# USBasp.net
KiCad netlist of a schematic drawn in EAGLE
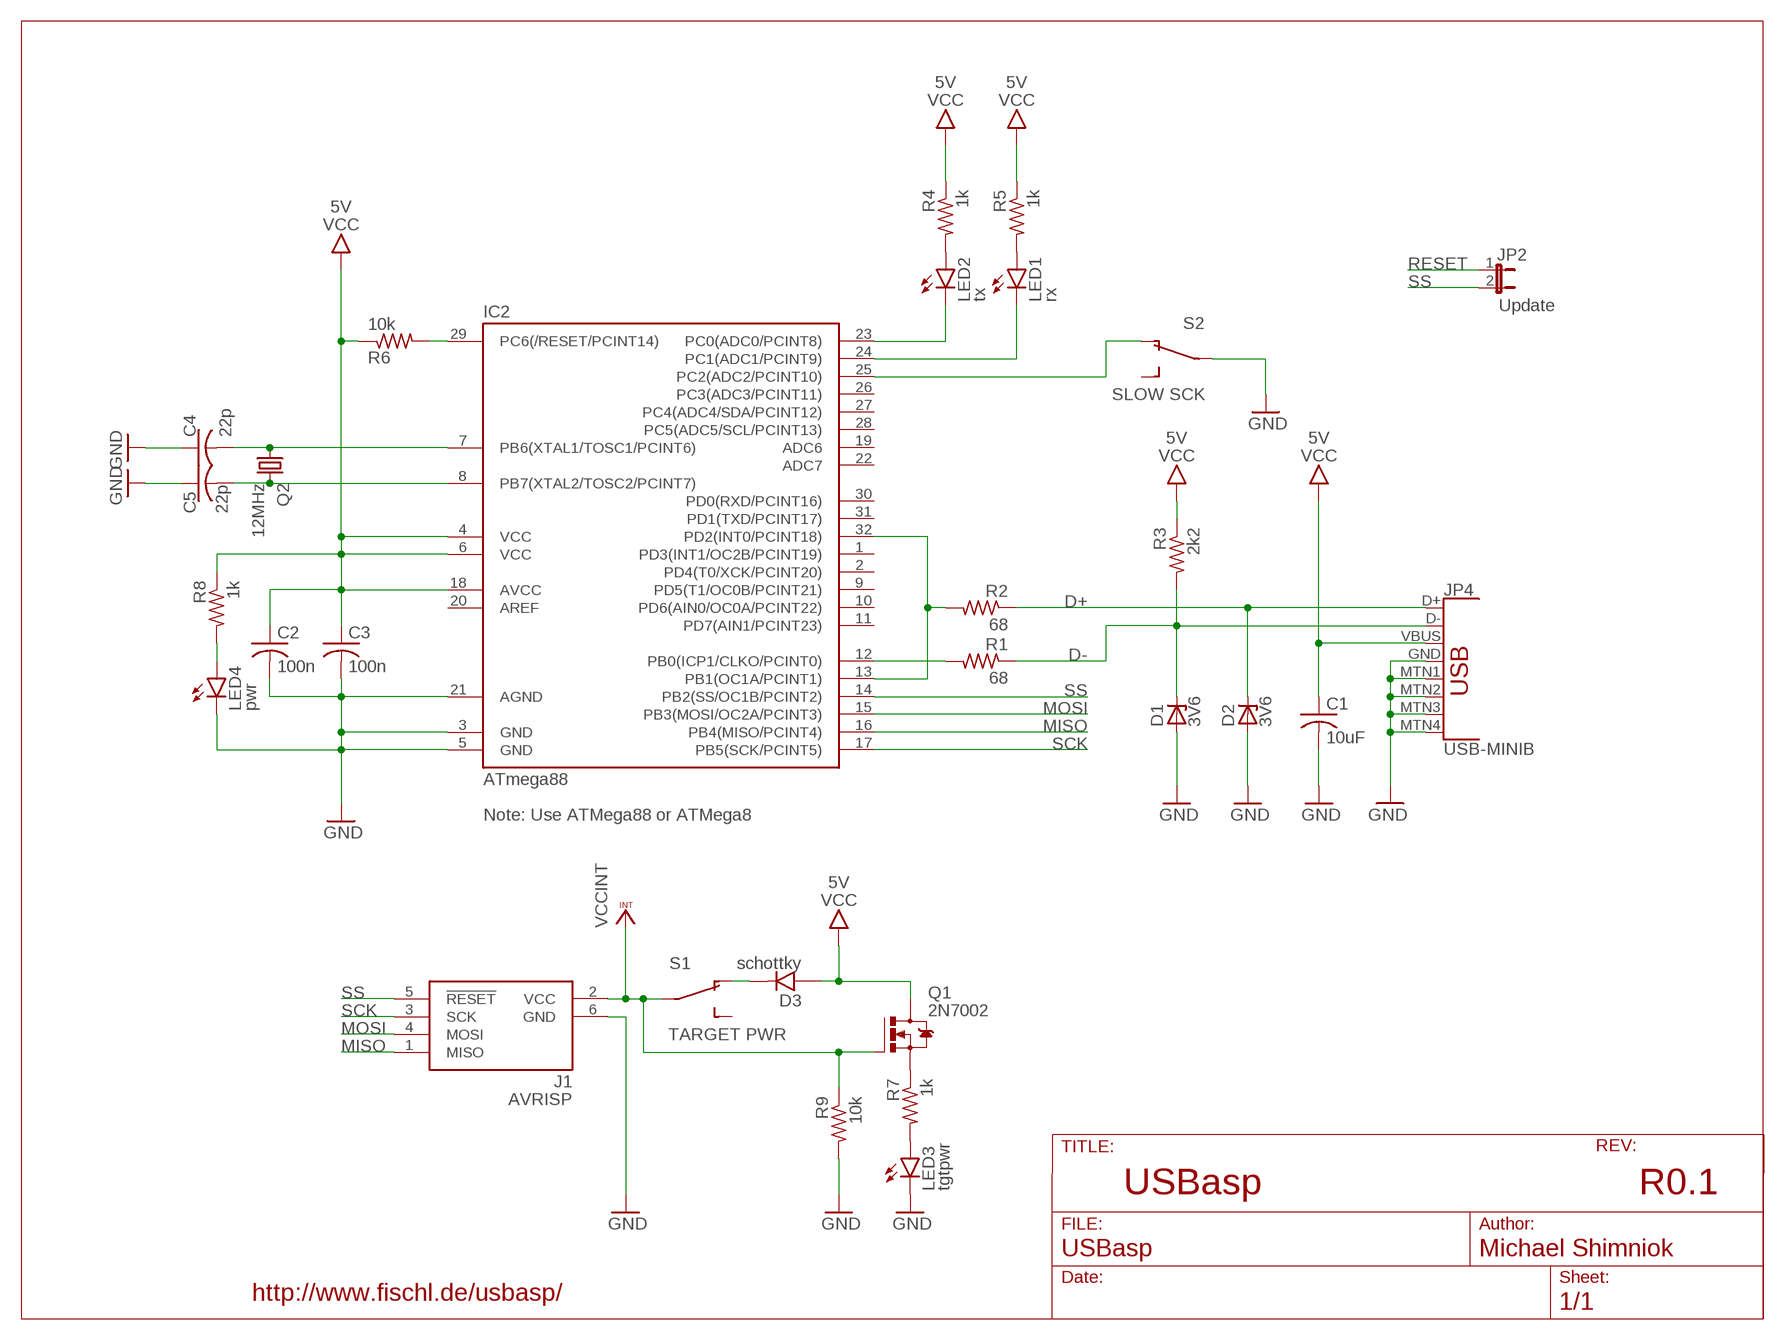
[diagram p0: schematic, sheet 1]

(export (version "E")
  (design (tool "Eeschema 10.0.6"))
  (components
    (comp (ref "C1")
      (value "10uF")
      (footprint "eagle-import:1206")
      (libsource (lib "eagle-import") (part "C-1206"))
    )
    (comp (ref "C2")
      (value "100n")
      (footprint "eagle-import:0603")
      (libsource (lib "eagle-import") (part "C-0603"))
    )
    (comp (ref "C3")
      (value "100n")
      (footprint "eagle-import:0603")
      (libsource (lib "eagle-import") (part "C-0603"))
    )
    (comp (ref "C4")
      (value "22p")
      (footprint "eagle-import:0603")
      (libsource (lib "eagle-import") (part "C-0603"))
    )
    (comp (ref "C5")
      (value "22p")
      (footprint "eagle-import:0603")
      (libsource (lib "eagle-import") (part "C-0603"))
    )
    (comp (ref "D1")
      (value "3V6")
      (footprint "eagle-import:SOD80C")
      (libsource (lib "eagle-import") (part "ZENER-DIODESOD80C"))
    )
    (comp (ref "D2")
      (value "3V6")
      (footprint "eagle-import:SOD80C")
      (libsource (lib "eagle-import") (part "ZENER-DIODESOD80C"))
    )
    (comp (ref "D3")
      (value "schottky")
      (footprint "eagle-import:SOD123FL")
      (libsource (lib "eagle-import") (part "DIODE_SOD123FL"))
    )
    (comp (ref "IC2")
      (value "ATmega88")
      (footprint "eagle-import:TQFP32-08")
      (libsource (lib "eagle-import") (part "MEGA48/88/168-AU"))
    )
    (comp (ref "J1")
      (value "AVRISP")
      (footprint "eagle-import:CON6P2R")
      (libsource (lib "eagle-import") (part "AVRISP6_COMPACT"))
    )
    (comp (ref "JP2")
      (value "Update")
      (footprint "eagle-import:JP1")
      (libsource (lib "eagle-import") (part "JP1E"))
    )
    (comp (ref "JP4")
      (value "USB-MINIB")
      (footprint "eagle-import:USB-MINIB")
      (libsource (lib "eagle-import") (part "USB-MINIB"))
    )
    (comp (ref "LED1")
      (value "rx")
      (footprint "eagle-import:CHIPLED_1206")
      (libsource (lib "eagle-import") (part "LEDCHIPLED_1206"))
    )
    (comp (ref "LED2")
      (value "tx")
      (footprint "eagle-import:CHIPLED_1206")
      (libsource (lib "eagle-import") (part "LEDCHIPLED_1206"))
    )
    (comp (ref "LED3")
      (value "tgtpwr")
      (footprint "eagle-import:CHIPLED_1206")
      (libsource (lib "eagle-import") (part "LEDCHIPLED_1206"))
    )
    (comp (ref "LED4")
      (value "pwr")
      (footprint "eagle-import:CHIPLED_1206")
      (libsource (lib "eagle-import") (part "LEDCHIPLED_1206"))
    )
    (comp (ref "Q1")
      (value "2N7002")
      (footprint "eagle-import:SOT-23")
      (libsource (lib "eagle-import") (part "MOSFET-N-SOT23"))
    )
    (comp (ref "Q2")
      (value "12MHz")
      (footprint "eagle-import:NDK_2PAD_5X3")
      (libsource (lib "eagle-import") (part "CRYSTALNDK5X3"))
    )
    (comp (ref "R1")
      (value "68")
      (footprint "eagle-import:0603")
      (libsource (lib "eagle-import") (part "R0603"))
    )
    (comp (ref "R2")
      (value "68")
      (footprint "eagle-import:0603")
      (libsource (lib "eagle-import") (part "R0603"))
    )
    (comp (ref "R3")
      (value "2k2")
      (footprint "eagle-import:0603")
      (libsource (lib "eagle-import") (part "R0603"))
    )
    (comp (ref "R4")
      (value "1k")
      (footprint "eagle-import:0603")
      (libsource (lib "eagle-import") (part "R0603"))
    )
    (comp (ref "R5")
      (value "1k")
      (footprint "eagle-import:0603")
      (libsource (lib "eagle-import") (part "R0603"))
    )
    (comp (ref "R6")
      (value "10k")
      (footprint "eagle-import:0603")
      (libsource (lib "eagle-import") (part "R0603"))
    )
    (comp (ref "R7")
      (value "1k")
      (footprint "eagle-import:0603")
      (libsource (lib "eagle-import") (part "R0603"))
    )
    (comp (ref "R8")
      (value "1k")
      (footprint "eagle-import:0603")
      (libsource (lib "eagle-import") (part "R0603"))
    )
    (comp (ref "R9")
      (value "10k")
      (footprint "eagle-import:0603")
      (libsource (lib "eagle-import") (part "R0603"))
    )
    (comp (ref "S1")
      (value "TARGET PWR")
      (footprint "eagle-import:OS102011MA1Q")
      (libsource (lib "eagle-import") (part "SPDT_OS102011MAQN1"))
    )
    (comp (ref "S2")
      (value "SLOW SCK")
      (footprint "eagle-import:OS102011MA1Q")
      (libsource (lib "eagle-import") (part "SPDT_OS102011MAQN1"))
    )
  )
  (nets
    (net (code "1") (name "/D+") (class "Default")
      (node (ref "D2") (pin "C") (pinfunction "C_C") (pintype "passive"))
      (node (ref "JP4") (pin "D+") (pinfunction "D+_D+") (pintype "bidirectional"))
      (node (ref "R2") (pin "1") (pinfunction "1_1") (pintype "passive"))
    )
    (net (code "2") (name "/D-") (class "Default")
      (node (ref "D1") (pin "C") (pinfunction "C_C") (pintype "passive"))
      (node (ref "JP4") (pin "D-") (pinfunction "D-_D-") (pintype "bidirectional"))
      (node (ref "R1") (pin "1") (pinfunction "1_1") (pintype "passive"))
      (node (ref "R3") (pin "2") (pinfunction "2_2") (pintype "passive"))
    )
    (net (code "3") (name "/MISO") (class "Default")
      (node (ref "IC2") (pin "16") (pinfunction "PB4(MISO/PCINT4)_16") (pintype "bidirectional"))
      (node (ref "J1") (pin "1") (pinfunction "MISO_1") (pintype "input"))
    )
    (net (code "4") (name "/MOSI") (class "Default")
      (node (ref "IC2") (pin "15") (pinfunction "PB3(MOSI/OC2A/PCINT3)_15") (pintype "bidirectional"))
      (node (ref "J1") (pin "4") (pinfunction "MOSI_4") (pintype "output"))
    )
    (net (code "5") (name "/RESET") (class "Default")
      (node (ref "IC2") (pin "29") (pinfunction "PC6(/RESET/PCINT14)_29") (pintype "bidirectional"))
      (node (ref "JP2") (pin "1") (pinfunction "1_1") (pintype "passive"))
      (node (ref "R6") (pin "2") (pinfunction "2_2") (pintype "passive"))
    )
    (net (code "6") (name "/SCK") (class "Default")
      (node (ref "IC2") (pin "17") (pinfunction "PB5(SCK/PCINT5)_17") (pintype "bidirectional"))
      (node (ref "J1") (pin "3") (pinfunction "SCK_3") (pintype "output"))
    )
    (net (code "7") (name "/SS") (class "Default")
      (node (ref "IC2") (pin "14") (pinfunction "PB2(SS/OC1B/PCINT2)_14") (pintype "bidirectional"))
      (node (ref "J1") (pin "5") (pinfunction "~{RESET}_5") (pintype "output"))
      (node (ref "JP2") (pin "2") (pinfunction "2_2") (pintype "passive"))
    )
    (net (code "8") (name "5V") (class "Default")
      (node (ref "C1") (pin "1") (pinfunction "+_1") (pintype "passive"))
      (node (ref "C2") (pin "1") (pinfunction "+_1") (pintype "passive"))
      (node (ref "C3") (pin "1") (pinfunction "+_1") (pintype "passive"))
      (node (ref "D3") (pin "A") (pinfunction "A_A") (pintype "passive"))
      (node (ref "IC2") (pin "18") (pinfunction "AVCC_18") (pintype "passive"))
      (node (ref "IC2") (pin "4") (pinfunction "VCC_4") (pintype "power_in"))
      (node (ref "IC2") (pin "6") (pinfunction "VCC_6") (pintype "power_in"))
      (node (ref "JP4") (pin "VBUS") (pinfunction "VBUS_VBUS") (pintype "bidirectional"))
      (node (ref "Q1") (pin "3") (pinfunction "D_3") (pintype "passive"))
      (node (ref "R3") (pin "1") (pinfunction "1_1") (pintype "passive"))
      (node (ref "R4") (pin "1") (pinfunction "1_1") (pintype "passive"))
      (node (ref "R5") (pin "1") (pinfunction "1_1") (pintype "passive"))
      (node (ref "R6") (pin "1") (pinfunction "1_1") (pintype "passive"))
      (node (ref "R8") (pin "1") (pinfunction "1_1") (pintype "passive"))
    )
    (net (code "9") (name "GND") (class "Default")
      (node (ref "C1") (pin "2") (pinfunction "-_2") (pintype "passive"))
      (node (ref "C2") (pin "2") (pinfunction "-_2") (pintype "passive"))
      (node (ref "C3") (pin "2") (pinfunction "-_2") (pintype "passive"))
      (node (ref "C4") (pin "1") (pinfunction "+_1") (pintype "passive"))
      (node (ref "C5") (pin "1") (pinfunction "+_1") (pintype "passive"))
      (node (ref "D1") (pin "A") (pinfunction "A_A") (pintype "passive"))
      (node (ref "D2") (pin "A") (pinfunction "A_A") (pintype "passive"))
      (node (ref "IC2") (pin "21") (pinfunction "AGND_21") (pintype "power_in"))
      (node (ref "IC2") (pin "3") (pinfunction "GND_3") (pintype "power_in"))
      (node (ref "IC2") (pin "5") (pinfunction "GND_5") (pintype "power_in"))
      (node (ref "J1") (pin "6") (pinfunction "GND_6") (pintype "power_in"))
      (node (ref "JP4") (pin "GND") (pinfunction "GND_GND") (pintype "bidirectional"))
      (node (ref "JP4") (pin "MTN1") (pinfunction "SHIELD1_MTN1") (pintype "bidirectional"))
      (node (ref "JP4") (pin "MTN2") (pinfunction "SHIELD2_MTN2") (pintype "bidirectional"))
      (node (ref "JP4") (pin "MTN3") (pinfunction "SHIELD3_MTN3") (pintype "bidirectional"))
      (node (ref "JP4") (pin "MTN4") (pinfunction "SHIELD4_MTN4") (pintype "bidirectional"))
      (node (ref "LED3") (pin "C") (pinfunction "C_C") (pintype "passive"))
      (node (ref "LED4") (pin "C") (pinfunction "C_C") (pintype "passive"))
      (node (ref "R9") (pin "2") (pinfunction "2_2") (pintype "passive"))
      (node (ref "S2") (pin "2") (pinfunction "P_2") (pintype "passive"))
    )
    (net (code "10") (name "Net-(C4--)") (class "Default")
      (node (ref "C4") (pin "2") (pinfunction "-_2") (pintype "passive"))
      (node (ref "IC2") (pin "7") (pinfunction "PB6(XTAL1/TOSC1/PCINT6)_7") (pintype "bidirectional"))
      (node (ref "Q2") (pin "P$1") (pinfunction "1_P$1") (pintype "passive"))
    )
    (net (code "11") (name "Net-(C5--)") (class "Default")
      (node (ref "C5") (pin "2") (pinfunction "-_2") (pintype "passive"))
      (node (ref "IC2") (pin "8") (pinfunction "PB7(XTAL2/TOSC2/PCINT7)_8") (pintype "bidirectional"))
      (node (ref "Q2") (pin "P$2") (pinfunction "2_P$2") (pintype "passive"))
    )
    (net (code "12") (name "Net-(IC2-PB0(ICP1{slash}CLKO{slash}PCINT0))") (class "Default")
      (node (ref "IC2") (pin "12") (pinfunction "PB0(ICP1/CLKO/PCINT0)_12") (pintype "bidirectional"))
      (node (ref "R1") (pin "2") (pinfunction "2_2") (pintype "passive"))
    )
    (net (code "13") (name "Net-(IC2-PB1(OC1A{slash}PCINT1))") (class "Default")
      (node (ref "IC2") (pin "13") (pinfunction "PB1(OC1A/PCINT1)_13") (pintype "bidirectional"))
      (node (ref "IC2") (pin "32") (pinfunction "PD2(INT0/PCINT18)_32") (pintype "bidirectional"))
      (node (ref "R2") (pin "2") (pinfunction "2_2") (pintype "passive"))
    )
    (net (code "14") (name "Net-(IC2-PC0(ADC0{slash}PCINT8))") (class "Default")
      (node (ref "IC2") (pin "23") (pinfunction "PC0(ADC0/PCINT8)_23") (pintype "bidirectional"))
      (node (ref "LED2") (pin "C") (pinfunction "C_C") (pintype "passive"))
    )
    (net (code "15") (name "Net-(IC2-PC1(ADC1{slash}PCINT9))") (class "Default")
      (node (ref "IC2") (pin "24") (pinfunction "PC1(ADC1/PCINT9)_24") (pintype "bidirectional"))
      (node (ref "LED1") (pin "C") (pinfunction "C_C") (pintype "passive"))
    )
    (net (code "16") (name "Net-(IC2-PC2(ADC2{slash}PCINT10))") (class "Default")
      (node (ref "IC2") (pin "25") (pinfunction "PC2(ADC2/PCINT10)_25") (pintype "bidirectional"))
      (node (ref "S2") (pin "1") (pinfunction "O1_1") (pintype "passive"))
    )
    (net (code "17") (name "Net-(LED1-PadA)") (class "Default")
      (node (ref "LED1") (pin "A") (pinfunction "A_A") (pintype "passive"))
      (node (ref "R5") (pin "2") (pinfunction "2_2") (pintype "passive"))
    )
    (net (code "18") (name "Net-(LED2-PadA)") (class "Default")
      (node (ref "LED2") (pin "A") (pinfunction "A_A") (pintype "passive"))
      (node (ref "R4") (pin "2") (pinfunction "2_2") (pintype "passive"))
    )
    (net (code "19") (name "Net-(LED3-PadA)") (class "Default")
      (node (ref "LED3") (pin "A") (pinfunction "A_A") (pintype "passive"))
      (node (ref "R7") (pin "2") (pinfunction "2_2") (pintype "passive"))
    )
    (net (code "20") (name "Net-(LED4-PadA)") (class "Default")
      (node (ref "LED4") (pin "A") (pinfunction "A_A") (pintype "passive"))
      (node (ref "R8") (pin "2") (pinfunction "2_2") (pintype "passive"))
    )
    (net (code "21") (name "Net-(Q1-S)") (class "Default")
      (node (ref "Q1") (pin "2") (pinfunction "S_2") (pintype "passive"))
      (node (ref "R7") (pin "1") (pinfunction "1_1") (pintype "passive"))
    )
    (net (code "22") (name "Net-(S1-O1)") (class "Default")
      (node (ref "D3") (pin "C") (pinfunction "C_C") (pintype "passive"))
      (node (ref "S1") (pin "1") (pinfunction "O1_1") (pintype "passive"))
    )
    (net (code "23") (name "VCCINT") (class "Default")
      (node (ref "J1") (pin "2") (pinfunction "VCC_2") (pintype "power_in"))
      (node (ref "Q1") (pin "1") (pinfunction "G_1") (pintype "passive"))
      (node (ref "R9") (pin "1") (pinfunction "1_1") (pintype "passive"))
      (node (ref "S1") (pin "2") (pinfunction "P_2") (pintype "passive"))
    )
    (net (code "24") (name "unconnected-(IC2-ADC6-Pad19)") (class "Default")
      (node (ref "IC2") (pin "19") (pinfunction "ADC6_19") (pintype "passive"))
    )
    (net (code "25") (name "unconnected-(IC2-ADC7-Pad22)") (class "Default")
      (node (ref "IC2") (pin "22") (pinfunction "ADC7_22") (pintype "passive"))
    )
    (net (code "26") (name "unconnected-(IC2-AREF-Pad20)") (class "Default")
      (node (ref "IC2") (pin "20") (pinfunction "AREF_20") (pintype "passive"))
    )
    (net (code "27") (name "unconnected-(IC2-PC3(ADC3{slash}PCINT11)-Pad26)") (class "Default")
      (node (ref "IC2") (pin "26") (pinfunction "PC3(ADC3/PCINT11)_26") (pintype "bidirectional"))
    )
    (net (code "28") (name "unconnected-(IC2-PC4(ADC4{slash}SDA{slash}PCINT12)-Pad27)") (class "Default")
      (node (ref "IC2") (pin "27") (pinfunction "PC4(ADC4/SDA/PCINT12)_27") (pintype "bidirectional"))
    )
    (net (code "29") (name "unconnected-(IC2-PC5(ADC5{slash}SCL{slash}PCINT13)-Pad28)") (class "Default")
      (node (ref "IC2") (pin "28") (pinfunction "PC5(ADC5/SCL/PCINT13)_28") (pintype "bidirectional"))
    )
    (net (code "30") (name "unconnected-(IC2-PD0(RXD{slash}PCINT16)-Pad30)") (class "Default")
      (node (ref "IC2") (pin "30") (pinfunction "PD0(RXD/PCINT16)_30") (pintype "bidirectional"))
    )
    (net (code "31") (name "unconnected-(IC2-PD1(TXD{slash}PCINT17)-Pad31)") (class "Default")
      (node (ref "IC2") (pin "31") (pinfunction "PD1(TXD/PCINT17)_31") (pintype "bidirectional"))
    )
    (net (code "32") (name "unconnected-(IC2-PD3(INT1{slash}OC2B{slash}PCINT19)-Pad1)") (class "Default")
      (node (ref "IC2") (pin "1") (pinfunction "PD3(INT1/OC2B/PCINT19)_1") (pintype "bidirectional"))
    )
    (net (code "33") (name "unconnected-(IC2-PD4(T0{slash}XCK{slash}PCINT20)-Pad2)") (class "Default")
      (node (ref "IC2") (pin "2") (pinfunction "PD4(T0/XCK/PCINT20)_2") (pintype "bidirectional"))
    )
    (net (code "34") (name "unconnected-(IC2-PD5(T1{slash}OC0B{slash}PCINT21)-Pad9)") (class "Default")
      (node (ref "IC2") (pin "9") (pinfunction "PD5(T1/OC0B/PCINT21)_9") (pintype "bidirectional"))
    )
    (net (code "35") (name "unconnected-(IC2-PD6(AIN0{slash}OC0A{slash}PCINT22)-Pad10)") (class "Default")
      (node (ref "IC2") (pin "10") (pinfunction "PD6(AIN0/OC0A/PCINT22)_10") (pintype "bidirectional"))
    )
    (net (code "36") (name "unconnected-(IC2-PD7(AIN1{slash}PCINT23)-Pad11)") (class "Default")
      (node (ref "IC2") (pin "11") (pinfunction "PD7(AIN1/PCINT23)_11") (pintype "bidirectional"))
    )
    (net (code "37") (name "unconnected-(S1-O2-Pad3)") (class "Default")
      (node (ref "S1") (pin "3") (pinfunction "O2_3") (pintype "passive"))
    )
    (net (code "38") (name "unconnected-(S2-O2-Pad3)") (class "Default")
      (node (ref "S2") (pin "3") (pinfunction "O2_3") (pintype "passive"))
    )
  )
)
